# stm_board_f407.net
KiCad netlist of a schematic drawn in EAGLE
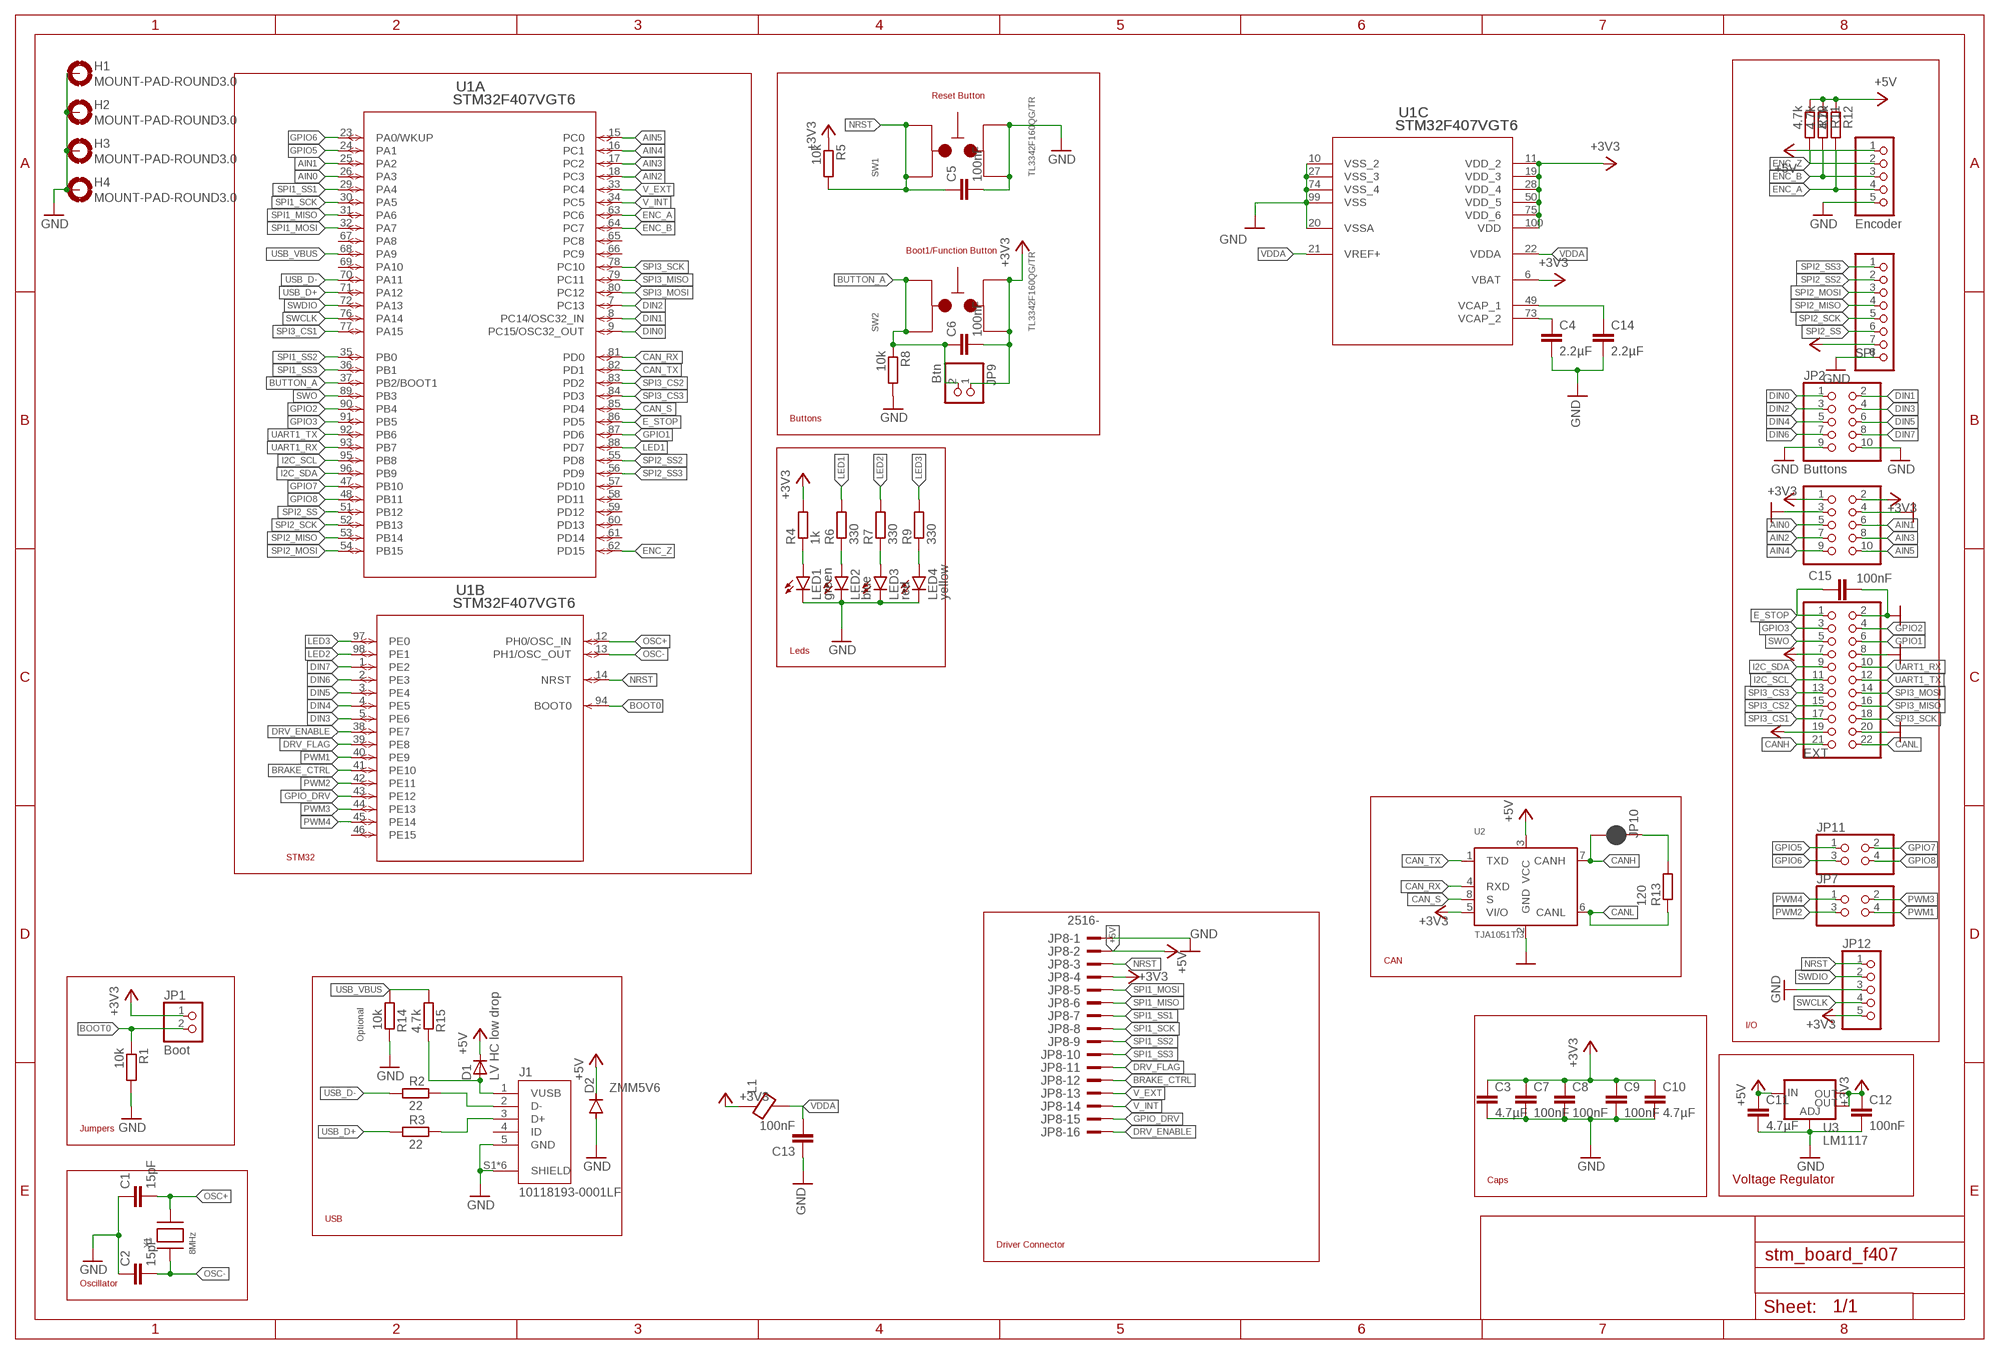
[diagram p0: schematic, sheet 1]

(export (version "E")
  (design (tool "Eeschema 10.0.6"))
  (components
    (comp (ref "C1")
      (value "15pF")
      (footprint "eagle-import:C0603")
      (libsource (lib "eagle-import") (part "C-EUC0603"))
    )
    (comp (ref "C2")
      (value "15pF")
      (footprint "eagle-import:C0603")
      (libsource (lib "eagle-import") (part "C-EUC0603"))
    )
    (comp (ref "C3")
      (value "4.7µF")
      (footprint "eagle-import:C0805")
      (libsource (lib "eagle-import") (part "C-EUC0805"))
    )
    (comp (ref "C4")
      (value "2.2µF")
      (footprint "eagle-import:C0603")
      (libsource (lib "eagle-import") (part "C-EUC0603"))
    )
    (comp (ref "C5")
      (value "100nF")
      (footprint "eagle-import:C0603")
      (libsource (lib "eagle-import") (part "C-EUC0603"))
    )
    (comp (ref "C6")
      (value "100nF")
      (footprint "eagle-import:C0603")
      (libsource (lib "eagle-import") (part "C-EUC0603"))
    )
    (comp (ref "C7")
      (value "100nF")
      (footprint "eagle-import:C0603")
      (libsource (lib "eagle-import") (part "C-EUC0603"))
    )
    (comp (ref "C8")
      (value "100nF")
      (footprint "eagle-import:C0603")
      (libsource (lib "eagle-import") (part "C-EUC0603"))
    )
    (comp (ref "C9")
      (value "100nF")
      (footprint "eagle-import:C0603")
      (libsource (lib "eagle-import") (part "C-EUC0603"))
    )
    (comp (ref "C10")
      (value "4.7µF")
      (footprint "eagle-import:C0805")
      (libsource (lib "eagle-import") (part "C-EUC0805"))
    )
    (comp (ref "C11")
      (value "4.7µF")
      (footprint "eagle-import:C0805")
      (libsource (lib "eagle-import") (part "C-EUC0805"))
    )
    (comp (ref "C12")
      (value "100nF")
      (footprint "eagle-import:C0603")
      (libsource (lib "eagle-import") (part "C-EUC0603"))
    )
    (comp (ref "C13")
      (value "100nF")
      (footprint "eagle-import:C0603")
      (libsource (lib "eagle-import") (part "C-EUC0603"))
    )
    (comp (ref "C14")
      (value "2.2µF")
      (footprint "eagle-import:C0603")
      (libsource (lib "eagle-import") (part "C-EUC0603"))
    )
    (comp (ref "C15")
      (value "100nF")
      (footprint "eagle-import:C0603")
      (libsource (lib "eagle-import") (part "C-EUC0603"))
    )
    (comp (ref "D1")
      (value "LV HC low drop")
      (footprint "eagle-import:SMADIODE")
      (libsource (lib "eagle-import") (part "DIODESMA"))
    )
    (comp (ref "D2")
      (value "ZMM5V6")
      (footprint "eagle-import:MINIMELF")
      (libsource (lib "eagle-import") (part "DIODE-MINIMELF"))
    )
    (comp (ref "H1")
      (value "MOUNT-PAD-ROUND3.0")
      (footprint "eagle-import:3,0-PAD")
      (libsource (lib "eagle-import") (part "MOUNT-PAD-ROUND3.0"))
    )
    (comp (ref "H2")
      (value "MOUNT-PAD-ROUND3.0")
      (footprint "eagle-import:3,0-PAD")
      (libsource (lib "eagle-import") (part "MOUNT-PAD-ROUND3.0"))
    )
    (comp (ref "H3")
      (value "MOUNT-PAD-ROUND3.0")
      (footprint "eagle-import:3,0-PAD")
      (libsource (lib "eagle-import") (part "MOUNT-PAD-ROUND3.0"))
    )
    (comp (ref "H4")
      (value "MOUNT-PAD-ROUND3.0")
      (footprint "eagle-import:3,0-PAD")
      (libsource (lib "eagle-import") (part "MOUNT-PAD-ROUND3.0"))
    )
    (comp (ref "J1")
      (value "10118193-0001LF")
      (footprint "eagle-import:FCI_10118193-0001LF")
      (fields (field (name "MF") "Amphenol ICC"))
      (libsource (lib "eagle-import") (part "10118193-0001LF"))
    )
    (comp (ref "JP1")
      (value "Boot")
      (footprint "eagle-import:1X02")
      (libsource (lib "eagle-import") (part "PINHD-1X2"))
    )
    (comp (ref "JP2")
      (value "Buttons")
      (footprint "eagle-import:2X05")
      (libsource (lib "eagle-import") (part "PINHD-2X5"))
    )
    (comp (ref "JP3")
      (value "Analog")
      (footprint "eagle-import:2X05")
      (libsource (lib "eagle-import") (part "PINHD-2X5"))
    )
    (comp (ref "JP4")
      (value "EXT")
      (footprint "eagle-import:2X11")
      (libsource (lib "eagle-import") (part "PINHD-2X11"))
    )
    (comp (ref "JP5")
      (value "Encoder")
      (footprint "eagle-import:1X05")
      (libsource (lib "eagle-import") (part "PINHD-1X5"))
    )
    (comp (ref "JP6")
      (value "SPI")
      (footprint "eagle-import:1X08")
      (libsource (lib "eagle-import") (part "PINHD-1X8"))
    )
    (comp (ref "JP7")
      (value "PINHD-2X2")
      (footprint "eagle-import:2X02")
      (libsource (lib "eagle-import") (part "PINHD-2X2"))
    )
    (comp (ref "JP8")
      (value "2516-")
      (footprint "eagle-import:PAK100_2500-16")
      (libsource (lib "eagle-import") (part "2516-"))
    )
    (comp (ref "JP9")
      (value "Btn")
      (footprint "eagle-import:1X02")
      (libsource (lib "eagle-import") (part "PINHD-1X2"))
    )
    (comp (ref "JP10")
      (value "JUMPER-SMT_2_NC_PASTE_NO-SILK")
      (footprint "eagle-import:SMT-JUMPER_2_NC_PASTE_NO-SILK")
      (libsource (lib "eagle-import") (part "JUMPER-SMT_2_NC_PASTE_NO-SILK"))
    )
    (comp (ref "JP11")
      (value "PINHD-2X2")
      (footprint "eagle-import:2X02")
      (libsource (lib "eagle-import") (part "PINHD-2X2"))
    )
    (comp (ref "JP12")
      (value "PINHD-1X5")
      (footprint "eagle-import:1X05")
      (libsource (lib "eagle-import") (part "PINHD-1X5"))
    )
    (comp (ref "L1")
      (value "GZ2012D601TF")
      (footprint "eagle-import:BLM21PG331SN1D")
      (fields
        (field (name "DIGIKEY_PART_NUMBER") "490-5988-2-ND")
        (field (name "MANUFACTURER") "Murata Electronics North America")
        (field (name "MPN") "BLM21PG331SN1D")
        (field (name "CREATED_BY") "PCBLayout.com")
      )
      (libsource (lib "eagle-import") (part "BLM21PG331SN1D"))
    )
    (comp (ref "LED1")
      (value "green")
      (footprint "eagle-import:SML0805")
      (libsource (lib "eagle-import") (part "LEDSML0805"))
    )
    (comp (ref "LED2")
      (value "blue")
      (footprint "eagle-import:SML0805")
      (libsource (lib "eagle-import") (part "LEDSML0805"))
    )
    (comp (ref "LED3")
      (value "red")
      (footprint "eagle-import:SML0805")
      (libsource (lib "eagle-import") (part "LEDSML0805"))
    )
    (comp (ref "LED4")
      (value "yellow")
      (footprint "eagle-import:SML0805")
      (libsource (lib "eagle-import") (part "LEDSML0805"))
    )
    (comp (ref "R1")
      (value "10k")
      (footprint "eagle-import:R0603")
      (libsource (lib "eagle-import") (part "R-EU_R0603"))
    )
    (comp (ref "R2")
      (value "22")
      (footprint "eagle-import:R0603")
      (libsource (lib "eagle-import") (part "R-EU_R0603"))
    )
    (comp (ref "R3")
      (value "22")
      (footprint "eagle-import:R0603")
      (libsource (lib "eagle-import") (part "R-EU_R0603"))
    )
    (comp (ref "R4")
      (value "1k")
      (footprint "eagle-import:R0603")
      (libsource (lib "eagle-import") (part "R-EU_R0603"))
    )
    (comp (ref "R5")
      (value "10k")
      (footprint "eagle-import:R0603")
      (libsource (lib "eagle-import") (part "R-EU_R0603"))
    )
    (comp (ref "R6")
      (value "330")
      (footprint "eagle-import:R0603")
      (libsource (lib "eagle-import") (part "R-EU_R0603"))
    )
    (comp (ref "R7")
      (value "330")
      (footprint "eagle-import:R0603")
      (libsource (lib "eagle-import") (part "R-EU_R0603"))
    )
    (comp (ref "R8")
      (value "10k")
      (footprint "eagle-import:R0603")
      (libsource (lib "eagle-import") (part "R-EU_R0603"))
    )
    (comp (ref "R9")
      (value "330")
      (footprint "eagle-import:R0603")
      (libsource (lib "eagle-import") (part "R-EU_R0603"))
    )
    (comp (ref "R10")
      (value "4.7k")
      (footprint "eagle-import:R0603")
      (libsource (lib "eagle-import") (part "R-EU_R0603"))
    )
    (comp (ref "R11")
      (value "4.7k")
      (footprint "eagle-import:R0603")
      (libsource (lib "eagle-import") (part "R-EU_R0603"))
    )
    (comp (ref "R12")
      (value "4.7k")
      (footprint "eagle-import:R0603")
      (libsource (lib "eagle-import") (part "R-EU_R0603"))
    )
    (comp (ref "R13")
      (value "120")
      (footprint "eagle-import:R0603")
      (libsource (lib "eagle-import") (part "R-EU_R0603"))
    )
    (comp (ref "R14")
      (value "10k")
      (footprint "eagle-import:R0603")
      (libsource (lib "eagle-import") (part "R-EU_R0603"))
    )
    (comp (ref "R15")
      (value "4.7k")
      (footprint "eagle-import:R0603")
      (libsource (lib "eagle-import") (part "R-EU_R0603"))
    )
    (comp (ref "SW1")
      (value "TL3342F160QG/TR")
      (footprint "eagle-import:TL3342F160QG_TR")
      (fields
        (field (name "DIGI_KEY_PART_NUMBER") "EG2531CT-ND")
        (field (name "MANUFACTURER") "E-Switch")
        (field (name "CREATED_BY") "PCBLayout.com")
      )
      (libsource (lib "eagle-import") (part "TL3342F160QG/TR"))
    )
    (comp (ref "SW2")
      (value "TL3342F160QG/TR")
      (footprint "eagle-import:TL3342F160QG_TR")
      (fields
        (field (name "DIGI_KEY_PART_NUMBER") "EG2531CT-ND")
        (field (name "MANUFACTURER") "E-Switch")
        (field (name "CREATED_BY") "PCBLayout.com")
      )
      (libsource (lib "eagle-import") (part "TL3342F160QG/TR"))
    )
    (comp (ref "U1")
      (value "STM32F407VGT6")
      (footprint "eagle-import:LQFP100-14X14MM")
      (fields (field (name "COPYRIGHT") "Copyright (C) 2018 Accelerated Designs. All rights reserved"))
      (libsource (lib "eagle-import") (part "STM32F407VGT6"))
    )
    (comp (ref "U2")
      (value "TJA1051T/3")
      (footprint "eagle-import:SOT96-1")
      (fields (field (name "MF") "NXP Semiconductors"))
      (libsource (lib "eagle-import") (part "TJA1051T/3"))
    )
    (comp (ref "U3")
      (value "LM1117")
      (footprint "eagle-import:SOT223")
      (libsource (lib "eagle-import") (part "V_REG_LM1117SOT223"))
    )
    (comp (ref "X1")
      (value "8MHz")
      (footprint "eagle-import:NX5032")
      (libsource (lib "eagle-import") (part "XTALNX5032"))
    )
  )
  (nets
    (net (code "1") (name "+3V3") (class "Default")
      (node (ref "C10") (pin "1") (pinfunction "1_1") (pintype "passive"))
      (node (ref "C12") (pin "1") (pinfunction "1_1") (pintype "passive"))
      (node (ref "C3") (pin "1") (pinfunction "1_1") (pintype "passive"))
      (node (ref "C6") (pin "2") (pinfunction "2_2") (pintype "passive"))
      (node (ref "C7") (pin "1") (pinfunction "1_1") (pintype "passive"))
      (node (ref "C8") (pin "1") (pinfunction "1_1") (pintype "passive"))
      (node (ref "C9") (pin "1") (pinfunction "1_1") (pintype "passive"))
      (node (ref "JP1") (pin "1") (pinfunction "1_1") (pintype "passive"))
      (node (ref "JP12") (pin "5") (pinfunction "5_5") (pintype "passive"))
      (node (ref "JP3") (pin "1") (pinfunction "1_1") (pintype "passive"))
      (node (ref "JP3") (pin "2") (pinfunction "2_2") (pintype "passive"))
      (node (ref "JP4") (pin "7") (pinfunction "7_7") (pintype "passive"))
      (node (ref "JP6") (pin "7") (pinfunction "7_7") (pintype "passive"))
      (node (ref "JP8") (pin "4") (pinfunction "KL_4") (pintype "passive"))
      (node (ref "JP9") (pin "1") (pinfunction "1_1") (pintype "passive"))
      (node (ref "L1") (pin "1") (pinfunction "1_1") (pintype "passive"))
      (node (ref "R4") (pin "2") (pinfunction "2_2") (pintype "passive"))
      (node (ref "R5") (pin "1") (pinfunction "1_1") (pintype "passive"))
      (node (ref "SW2") (pin "1") (pinfunction "1_1") (pintype "passive"))
      (node (ref "SW2") (pin "2") (pinfunction "2_2") (pintype "passive"))
      (node (ref "U1") (pin "100") (pinfunction "VDD_100") (pintype "power_in"))
      (node (ref "U1") (pin "11") (pinfunction "VDD_2_11") (pintype "power_in"))
      (node (ref "U1") (pin "19") (pinfunction "VDD_3_19") (pintype "power_in"))
      (node (ref "U1") (pin "28") (pinfunction "VDD_4_28") (pintype "power_in"))
      (node (ref "U1") (pin "50") (pinfunction "VDD_5_50") (pintype "power_in"))
      (node (ref "U1") (pin "6") (pinfunction "VBAT_6") (pintype "power_in"))
      (node (ref "U1") (pin "75") (pinfunction "VDD_6_75") (pintype "power_in"))
      (node (ref "U2") (pin "5") (pinfunction "VI/O_5") (pintype "passive"))
      (node (ref "U3") (pin "2") (pinfunction "OUT_2") (pintype "output"))
      (node (ref "U3") (pin "4") (pinfunction "OUT_4") (pintype "output"))
    )
    (net (code "2") (name "+5V") (class "Default")
      (node (ref "C11") (pin "1") (pinfunction "1_1") (pintype "passive"))
      (node (ref "D1") (pin "C") (pinfunction "C_C") (pintype "passive"))
      (node (ref "D2") (pin "C") (pinfunction "C_C") (pintype "passive"))
      (node (ref "JP4") (pin "19") (pinfunction "19_19") (pintype "passive"))
      (node (ref "JP5") (pin "1") (pinfunction "1_1") (pintype "passive"))
      (node (ref "JP8") (pin "2") (pinfunction "KL_2") (pintype "passive"))
      (node (ref "R10") (pin "1") (pinfunction "1_1") (pintype "passive"))
      (node (ref "R11") (pin "1") (pinfunction "1_1") (pintype "passive"))
      (node (ref "R12") (pin "1") (pinfunction "1_1") (pintype "passive"))
      (node (ref "U2") (pin "3") (pinfunction "VCC_3") (pintype "bidirectional"))
      (node (ref "U3") (pin "3") (pinfunction "IN_3") (pintype "input"))
    )
    (net (code "3") (name "AIN0") (class "Default")
      (node (ref "JP3") (pin "5") (pinfunction "5_5") (pintype "passive"))
      (node (ref "U1") (pin "26") (pinfunction "PA3_26") (pintype "bidirectional"))
    )
    (net (code "4") (name "AIN1") (class "Default")
      (node (ref "JP3") (pin "6") (pinfunction "6_6") (pintype "passive"))
      (node (ref "U1") (pin "25") (pinfunction "PA2_25") (pintype "bidirectional"))
    )
    (net (code "5") (name "AIN2") (class "Default")
      (node (ref "JP3") (pin "7") (pinfunction "7_7") (pintype "passive"))
      (node (ref "U1") (pin "18") (pinfunction "PC3_18") (pintype "bidirectional"))
    )
    (net (code "6") (name "AIN3") (class "Default")
      (node (ref "JP3") (pin "8") (pinfunction "8_8") (pintype "passive"))
      (node (ref "U1") (pin "17") (pinfunction "PC2_17") (pintype "bidirectional"))
    )
    (net (code "7") (name "AIN4") (class "Default")
      (node (ref "JP3") (pin "9") (pinfunction "9_9") (pintype "passive"))
      (node (ref "U1") (pin "16") (pinfunction "PC1_16") (pintype "bidirectional"))
    )
    (net (code "8") (name "AIN5") (class "Default")
      (node (ref "JP3") (pin "10") (pinfunction "10_10") (pintype "passive"))
      (node (ref "U1") (pin "15") (pinfunction "PC0_15") (pintype "bidirectional"))
    )
    (net (code "9") (name "BOOT0") (class "Default")
      (node (ref "JP1") (pin "2") (pinfunction "2_2") (pintype "passive"))
      (node (ref "R1") (pin "1") (pinfunction "1_1") (pintype "passive"))
      (node (ref "U1") (pin "94") (pinfunction "BOOT0_94") (pintype "input"))
    )
    (net (code "10") (name "BRAKE_CTRL") (class "Default")
      (node (ref "JP8") (pin "12") (pinfunction "KL_12") (pintype "passive"))
      (node (ref "U1") (pin "41") (pinfunction "PE10_41") (pintype "bidirectional"))
    )
    (net (code "11") (name "BUTTON_A") (class "Default")
      (node (ref "C6") (pin "1") (pinfunction "1_1") (pintype "passive"))
      (node (ref "JP9") (pin "2") (pinfunction "2_2") (pintype "passive"))
      (node (ref "R8") (pin "1") (pinfunction "1_1") (pintype "passive"))
      (node (ref "SW2") (pin "3") (pinfunction "3_3") (pintype "passive"))
      (node (ref "SW2") (pin "4") (pinfunction "4_4") (pintype "passive"))
      (node (ref "U1") (pin "37") (pinfunction "PB2/BOOT1_37") (pintype "bidirectional"))
    )
    (net (code "12") (name "CANH") (class "Default")
      (node (ref "JP10") (pin "2") (pinfunction "2_2") (pintype "passive"))
      (node (ref "JP4") (pin "21") (pinfunction "21_21") (pintype "passive"))
      (node (ref "U2") (pin "7") (pinfunction "CANH_7") (pintype "bidirectional"))
    )
    (net (code "13") (name "CANL") (class "Default")
      (node (ref "JP4") (pin "22") (pinfunction "22_22") (pintype "passive"))
      (node (ref "R13") (pin "1") (pinfunction "1_1") (pintype "passive"))
      (node (ref "U2") (pin "6") (pinfunction "CANL_6") (pintype "bidirectional"))
    )
    (net (code "14") (name "CAN_RX") (class "Default")
      (node (ref "U1") (pin "81") (pinfunction "PD0_81") (pintype "bidirectional"))
      (node (ref "U2") (pin "4") (pinfunction "RXD_4") (pintype "bidirectional"))
    )
    (net (code "15") (name "CAN_S") (class "Default")
      (node (ref "U1") (pin "85") (pinfunction "PD4_85") (pintype "bidirectional"))
      (node (ref "U2") (pin "8") (pinfunction "S_8") (pintype "power_in"))
    )
    (net (code "16") (name "CAN_TX") (class "Default")
      (node (ref "U1") (pin "82") (pinfunction "PD1_82") (pintype "bidirectional"))
      (node (ref "U2") (pin "1") (pinfunction "TXD_1") (pintype "output"))
    )
    (net (code "17") (name "DIN0") (class "Default")
      (node (ref "JP2") (pin "1") (pinfunction "1_1") (pintype "passive"))
      (node (ref "U1") (pin "9") (pinfunction "PC15/OSC32_OUT_9") (pintype "bidirectional"))
    )
    (net (code "18") (name "DIN1") (class "Default")
      (node (ref "JP2") (pin "2") (pinfunction "2_2") (pintype "passive"))
      (node (ref "U1") (pin "8") (pinfunction "PC14/OSC32_IN_8") (pintype "bidirectional"))
    )
    (net (code "19") (name "DIN2") (class "Default")
      (node (ref "JP2") (pin "3") (pinfunction "3_3") (pintype "passive"))
      (node (ref "U1") (pin "7") (pinfunction "PC13_7") (pintype "bidirectional"))
    )
    (net (code "20") (name "DIN3") (class "Default")
      (node (ref "JP2") (pin "4") (pinfunction "4_4") (pintype "passive"))
      (node (ref "U1") (pin "5") (pinfunction "PE6_5") (pintype "bidirectional"))
    )
    (net (code "21") (name "DIN4") (class "Default")
      (node (ref "JP2") (pin "5") (pinfunction "5_5") (pintype "passive"))
      (node (ref "U1") (pin "4") (pinfunction "PE5_4") (pintype "bidirectional"))
    )
    (net (code "22") (name "DIN5") (class "Default")
      (node (ref "JP2") (pin "6") (pinfunction "6_6") (pintype "passive"))
      (node (ref "U1") (pin "3") (pinfunction "PE4_3") (pintype "bidirectional"))
    )
    (net (code "23") (name "DIN6") (class "Default")
      (node (ref "JP2") (pin "7") (pinfunction "7_7") (pintype "passive"))
      (node (ref "U1") (pin "2") (pinfunction "PE3_2") (pintype "bidirectional"))
    )
    (net (code "24") (name "DIN7") (class "Default")
      (node (ref "JP2") (pin "8") (pinfunction "8_8") (pintype "passive"))
      (node (ref "U1") (pin "1") (pinfunction "PE2_1") (pintype "bidirectional"))
    )
    (net (code "25") (name "DRV_ENABLE") (class "Default")
      (node (ref "JP8") (pin "16") (pinfunction "KL_16") (pintype "passive"))
      (node (ref "U1") (pin "38") (pinfunction "PE7_38") (pintype "bidirectional"))
    )
    (net (code "26") (name "DRV_FLAG") (class "Default")
      (node (ref "JP8") (pin "11") (pinfunction "KL_11") (pintype "passive"))
      (node (ref "U1") (pin "39") (pinfunction "PE8_39") (pintype "bidirectional"))
    )
    (net (code "27") (name "ENC_A") (class "Default")
      (node (ref "JP5") (pin "4") (pinfunction "4_4") (pintype "passive"))
      (node (ref "R12") (pin "2") (pinfunction "2_2") (pintype "passive"))
      (node (ref "U1") (pin "63") (pinfunction "PC6_63") (pintype "bidirectional"))
    )
    (net (code "28") (name "ENC_B") (class "Default")
      (node (ref "JP5") (pin "3") (pinfunction "3_3") (pintype "passive"))
      (node (ref "R11") (pin "2") (pinfunction "2_2") (pintype "passive"))
      (node (ref "U1") (pin "64") (pinfunction "PC7_64") (pintype "bidirectional"))
    )
    (net (code "29") (name "ENC_Z") (class "Default")
      (node (ref "JP5") (pin "2") (pinfunction "2_2") (pintype "passive"))
      (node (ref "R10") (pin "2") (pinfunction "2_2") (pintype "passive"))
      (node (ref "U1") (pin "62") (pinfunction "PD15_62") (pintype "bidirectional"))
    )
    (net (code "30") (name "E_STOP") (class "Default")
      (node (ref "C15") (pin "1") (pinfunction "1_1") (pintype "passive"))
      (node (ref "JP4") (pin "1") (pinfunction "1_1") (pintype "passive"))
      (node (ref "U1") (pin "86") (pinfunction "PD5_86") (pintype "bidirectional"))
    )
    (net (code "31") (name "GND") (class "Default")
      (node (ref "C1") (pin "1") (pinfunction "1_1") (pintype "passive"))
      (node (ref "C10") (pin "2") (pinfunction "2_2") (pintype "passive"))
      (node (ref "C11") (pin "2") (pinfunction "2_2") (pintype "passive"))
      (node (ref "C12") (pin "2") (pinfunction "2_2") (pintype "passive"))
      (node (ref "C13") (pin "1") (pinfunction "1_1") (pintype "passive"))
      (node (ref "C14") (pin "2") (pinfunction "2_2") (pintype "passive"))
      (node (ref "C15") (pin "2") (pinfunction "2_2") (pintype "passive"))
      (node (ref "C2") (pin "1") (pinfunction "1_1") (pintype "passive"))
      (node (ref "C3") (pin "2") (pinfunction "2_2") (pintype "passive"))
      (node (ref "C4") (pin "2") (pinfunction "2_2") (pintype "passive"))
      (node (ref "C5") (pin "2") (pinfunction "2_2") (pintype "passive"))
      (node (ref "C7") (pin "2") (pinfunction "2_2") (pintype "passive"))
      (node (ref "C8") (pin "2") (pinfunction "2_2") (pintype "passive"))
      (node (ref "C9") (pin "2") (pinfunction "2_2") (pintype "passive"))
      (node (ref "D2") (pin "A") (pinfunction "A_A") (pintype "passive"))
      (node (ref "H1") (pin "B3,0") (pinfunction "MOUNT_B3,0") (pintype "passive"))
      (node (ref "H2") (pin "B3,0") (pinfunction "MOUNT_B3,0") (pintype "passive"))
      (node (ref "H3") (pin "B3,0") (pinfunction "MOUNT_B3,0") (pintype "passive"))
      (node (ref "H4") (pin "B3,0") (pinfunction "MOUNT_B3,0") (pintype "passive"))
      (node (ref "J1") (pin "5") (pinfunction "GND_5") (pintype "passive"))
      (node (ref "J1") (pin "S1") (pinfunction "SHIELD_S1") (pintype "passive"))
      (node (ref "J1") (pin "S2") (pinfunction "SHIELD_S2") (pintype "passive"))
      (node (ref "J1") (pin "S3") (pinfunction "SHIELD_S3") (pintype "passive"))
      (node (ref "J1") (pin "S4") (pinfunction "SHIELD_S4") (pintype "passive"))
      (node (ref "J1") (pin "S5") (pinfunction "SHIELD_S5") (pintype "passive"))
      (node (ref "J1") (pin "S6") (pinfunction "SHIELD_S6") (pintype "passive"))
      (node (ref "JP12") (pin "3") (pinfunction "3_3") (pintype "passive"))
      (node (ref "JP2") (pin "10") (pinfunction "10_10") (pintype "passive"))
      (node (ref "JP2") (pin "9") (pinfunction "9_9") (pintype "passive"))
      (node (ref "JP3") (pin "3") (pinfunction "3_3") (pintype "passive"))
      (node (ref "JP3") (pin "4") (pinfunction "4_4") (pintype "passive"))
      (node (ref "JP4") (pin "2") (pinfunction "2_2") (pintype "passive"))
      (node (ref "JP4") (pin "20") (pinfunction "20_20") (pintype "passive"))
      (node (ref "JP4") (pin "8") (pinfunction "8_8") (pintype "passive"))
      (node (ref "JP5") (pin "5") (pinfunction "5_5") (pintype "passive"))
      (node (ref "JP6") (pin "8") (pinfunction "8_8") (pintype "passive"))
      (node (ref "JP8") (pin "1") (pinfunction "KL_1") (pintype "passive"))
      (node (ref "LED1") (pin "C") (pinfunction "C_C") (pintype "passive"))
      (node (ref "LED2") (pin "C") (pinfunction "C_C") (pintype "passive"))
      (node (ref "LED3") (pin "C") (pinfunction "C_C") (pintype "passive"))
      (node (ref "LED4") (pin "C") (pinfunction "C_C") (pintype "passive"))
      (node (ref "R1") (pin "2") (pinfunction "2_2") (pintype "passive"))
      (node (ref "R14") (pin "2") (pinfunction "2_2") (pintype "passive"))
      (node (ref "R8") (pin "2") (pinfunction "2_2") (pintype "passive"))
      (node (ref "SW1") (pin "1") (pinfunction "1_1") (pintype "passive"))
      (node (ref "SW1") (pin "2") (pinfunction "2_2") (pintype "passive"))
      (node (ref "U1") (pin "10") (pinfunction "VSS_2_10") (pintype "power_in"))
      (node (ref "U1") (pin "20") (pinfunction "VSSA_20") (pintype "power_in"))
      (node (ref "U1") (pin "27") (pinfunction "VSS_3_27") (pintype "power_in"))
      (node (ref "U1") (pin "74") (pinfunction "VSS_4_74") (pintype "power_in"))
      (node (ref "U1") (pin "99") (pinfunction "VSS_99") (pintype "power_in"))
      (node (ref "U2") (pin "2") (pinfunction "GND_2") (pintype "bidirectional"))
      (node (ref "U3") (pin "1") (pinfunction "ADJ_1") (pintype "input"))
    )
    (net (code "32") (name "GPIO1") (class "Default")
      (node (ref "JP4") (pin "6") (pinfunction "6_6") (pintype "passive"))
      (node (ref "U1") (pin "87") (pinfunction "PD6_87") (pintype "bidirectional"))
    )
    (net (code "33") (name "GPIO2") (class "Default")
      (node (ref "JP4") (pin "4") (pinfunction "4_4") (pintype "passive"))
      (node (ref "U1") (pin "90") (pinfunction "PB4_90") (pintype "bidirectional"))
    )
    (net (code "34") (name "GPIO3") (class "Default")
      (node (ref "JP4") (pin "3") (pinfunction "3_3") (pintype "passive"))
      (node (ref "U1") (pin "91") (pinfunction "PB5_91") (pintype "bidirectional"))
    )
    (net (code "35") (name "GPIO5") (class "Default")
      (node (ref "JP11") (pin "1") (pinfunction "1_1") (pintype "passive"))
      (node (ref "U1") (pin "24") (pinfunction "PA1_24") (pintype "bidirectional"))
    )
    (net (code "36") (name "GPIO6") (class "Default")
      (node (ref "JP11") (pin "3") (pinfunction "3_3") (pintype "passive"))
      (node (ref "U1") (pin "23") (pinfunction "PA0/WKUP_23") (pintype "bidirectional"))
    )
    (net (code "37") (name "GPIO7") (class "Default")
      (node (ref "JP11") (pin "2") (pinfunction "2_2") (pintype "passive"))
      (node (ref "U1") (pin "47") (pinfunction "PB10_47") (pintype "bidirectional"))
    )
    (net (code "38") (name "GPIO8") (class "Default")
      (node (ref "JP11") (pin "4") (pinfunction "4_4") (pintype "passive"))
      (node (ref "U1") (pin "48") (pinfunction "PB11_48") (pintype "bidirectional"))
    )
    (net (code "39") (name "GPIO_DRV") (class "Default")
      (node (ref "JP8") (pin "15") (pinfunction "KL_15") (pintype "passive"))
      (node (ref "U1") (pin "43") (pinfunction "PE12_43") (pintype "bidirectional"))
    )
    (net (code "40") (name "I2C_SCL") (class "Default")
      (node (ref "JP4") (pin "11") (pinfunction "11_11") (pintype "passive"))
      (node (ref "U1") (pin "95") (pinfunction "PB8_95") (pintype "bidirectional"))
    )
    (net (code "41") (name "I2C_SDA") (class "Default")
      (node (ref "JP4") (pin "9") (pinfunction "9_9") (pintype "passive"))
      (node (ref "U1") (pin "96") (pinfunction "PB9_96") (pintype "bidirectional"))
    )
    (net (code "42") (name "LED1") (class "Default")
      (node (ref "R6") (pin "2") (pinfunction "2_2") (pintype "passive"))
      (node (ref "U1") (pin "88") (pinfunction "PD7_88") (pintype "bidirectional"))
    )
    (net (code "43") (name "LED2") (class "Default")
      (node (ref "R7") (pin "2") (pinfunction "2_2") (pintype "passive"))
      (node (ref "U1") (pin "98") (pinfunction "PE1_98") (pintype "bidirectional"))
    )
    (net (code "44") (name "LED3") (class "Default")
      (node (ref "R9") (pin "2") (pinfunction "2_2") (pintype "passive"))
      (node (ref "U1") (pin "97") (pinfunction "PE0_97") (pintype "bidirectional"))
    )
    (net (code "45") (name "NRST") (class "Default")
      (node (ref "C5") (pin "1") (pinfunction "1_1") (pintype "passive"))
      (node (ref "JP12") (pin "1") (pinfunction "1_1") (pintype "passive"))
      (node (ref "JP8") (pin "3") (pinfunction "KL_3") (pintype "passive"))
      (node (ref "R5") (pin "2") (pinfunction "2_2") (pintype "passive"))
      (node (ref "SW1") (pin "3") (pinfunction "3_3") (pintype "passive"))
      (node (ref "SW1") (pin "4") (pinfunction "4_4") (pintype "passive"))
      (node (ref "U1") (pin "14") (pinfunction "NRST_14") (pintype "bidirectional"))
    )
    (net (code "46") (name "Net-(J1-D+)") (class "Default")
      (node (ref "J1") (pin "3") (pinfunction "D+_3") (pintype "passive"))
      (node (ref "R3") (pin "2") (pinfunction "2_2") (pintype "passive"))
    )
    (net (code "47") (name "Net-(J1-D-)") (class "Default")
      (node (ref "J1") (pin "2") (pinfunction "D-_2") (pintype "passive"))
      (node (ref "R2") (pin "2") (pinfunction "2_2") (pintype "passive"))
    )
    (net (code "48") (name "Net-(J1-VUSB)") (class "Default")
      (node (ref "D1") (pin "A") (pinfunction "A_A") (pintype "passive"))
      (node (ref "J1") (pin "1") (pinfunction "VUSB_1") (pintype "passive"))
      (node (ref "R15") (pin "2") (pinfunction "2_2") (pintype "passive"))
    )
    (net (code "49") (name "Net-(JP10-Pad1)") (class "Default")
      (node (ref "JP10") (pin "1") (pinfunction "1_1") (pintype "passive"))
      (node (ref "R13") (pin "2") (pinfunction "2_2") (pintype "passive"))
    )
    (net (code "50") (name "Net-(LED1-PadA)") (class "Default")
      (node (ref "LED1") (pin "A") (pinfunction "A_A") (pintype "passive"))
      (node (ref "R4") (pin "1") (pinfunction "1_1") (pintype "passive"))
    )
    (net (code "51") (name "Net-(LED2-PadA)") (class "Default")
      (node (ref "LED2") (pin "A") (pinfunction "A_A") (pintype "passive"))
      (node (ref "R6") (pin "1") (pinfunction "1_1") (pintype "passive"))
    )
    (net (code "52") (name "Net-(LED3-PadA)") (class "Default")
      (node (ref "LED3") (pin "A") (pinfunction "A_A") (pintype "passive"))
      (node (ref "R7") (pin "1") (pinfunction "1_1") (pintype "passive"))
    )
    (net (code "53") (name "Net-(LED4-PadA)") (class "Default")
      (node (ref "LED4") (pin "A") (pinfunction "A_A") (pintype "passive"))
      (node (ref "R9") (pin "1") (pinfunction "1_1") (pintype "passive"))
    )
    (net (code "54") (name "Net-(U1C-VCAP_1)") (class "Default")
      (node (ref "C14") (pin "1") (pinfunction "1_1") (pintype "passive"))
      (node (ref "U1") (pin "49") (pinfunction "VCAP_1_49") (pintype "power_in"))
    )
    (net (code "55") (name "Net-(U1C-VCAP_2)") (class "Default")
      (node (ref "C4") (pin "1") (pinfunction "1_1") (pintype "passive"))
      (node (ref "U1") (pin "73") (pinfunction "VCAP_2_73") (pintype "power_in"))
    )
    (net (code "56") (name "OSC+") (class "Default")
      (node (ref "C1") (pin "2") (pinfunction "2_2") (pintype "passive"))
      (node (ref "U1") (pin "12") (pinfunction "PH0/OSC_IN_12") (pintype "bidirectional"))
      (node (ref "X1") (pin "P$2") (pinfunction "P$2_P$2") (pintype "bidirectional"))
    )
    (net (code "57") (name "OSC-") (class "Default")
      (node (ref "C2") (pin "2") (pinfunction "2_2") (pintype "passive"))
      (node (ref "U1") (pin "13") (pinfunction "PH1/OSC_OUT_13") (pintype "bidirectional"))
      (node (ref "X1") (pin "P$1") (pinfunction "P$1_P$1") (pintype "bidirectional"))
    )
    (net (code "58") (name "PWM1") (class "Default")
      (node (ref "JP7") (pin "4") (pinfunction "4_4") (pintype "passive"))
      (node (ref "U1") (pin "40") (pinfunction "PE9_40") (pintype "bidirectional"))
    )
    (net (code "59") (name "PWM2") (class "Default")
      (node (ref "JP7") (pin "3") (pinfunction "3_3") (pintype "passive"))
      (node (ref "U1") (pin "42") (pinfunction "PE11_42") (pintype "bidirectional"))
    )
    (net (code "60") (name "PWM3") (class "Default")
      (node (ref "JP7") (pin "2") (pinfunction "2_2") (pintype "passive"))
      (node (ref "U1") (pin "44") (pinfunction "PE13_44") (pintype "bidirectional"))
    )
    (net (code "61") (name "PWM4") (class "Default")
      (node (ref "JP7") (pin "1") (pinfunction "1_1") (pintype "passive"))
      (node (ref "U1") (pin "45") (pinfunction "PE14_45") (pintype "bidirectional"))
    )
    (net (code "62") (name "SPI1_MISO") (class "Default")
      (node (ref "JP8") (pin "6") (pinfunction "KL_6") (pintype "passive"))
      (node (ref "U1") (pin "31") (pinfunction "PA6_31") (pintype "bidirectional"))
    )
    (net (code "63") (name "SPI1_MOSI") (class "Default")
      (node (ref "JP8") (pin "5") (pinfunction "KL_5") (pintype "passive"))
      (node (ref "U1") (pin "32") (pinfunction "PA7_32") (pintype "bidirectional"))
    )
    (net (code "64") (name "SPI1_SCK") (class "Default")
      (node (ref "JP8") (pin "8") (pinfunction "KL_8") (pintype "passive"))
      (node (ref "U1") (pin "30") (pinfunction "PA5_30") (pintype "bidirectional"))
    )
    (net (code "65") (name "SPI1_SS1") (class "Default")
      (node (ref "JP8") (pin "7") (pinfunction "KL_7") (pintype "passive"))
      (node (ref "U1") (pin "29") (pinfunction "PA4_29") (pintype "bidirectional"))
    )
    (net (code "66") (name "SPI1_SS2") (class "Default")
      (node (ref "JP8") (pin "9") (pinfunction "KL_9") (pintype "passive"))
      (node (ref "U1") (pin "35") (pinfunction "PB0_35") (pintype "bidirectional"))
    )
    (net (code "67") (name "SPI1_SS3") (class "Default")
      (node (ref "JP8") (pin "10") (pinfunction "KL_10") (pintype "passive"))
      (node (ref "U1") (pin "36") (pinfunction "PB1_36") (pintype "bidirectional"))
    )
    (net (code "68") (name "SPI2_MISO") (class "Default")
      (node (ref "JP6") (pin "4") (pinfunction "4_4") (pintype "passive"))
      (node (ref "U1") (pin "53") (pinfunction "PB14_53") (pintype "bidirectional"))
    )
    (net (code "69") (name "SPI2_MOSI") (class "Default")
      (node (ref "JP6") (pin "3") (pinfunction "3_3") (pintype "passive"))
      (node (ref "U1") (pin "54") (pinfunction "PB15_54") (pintype "bidirectional"))
    )
    (net (code "70") (name "SPI2_SCK") (class "Default")
      (node (ref "JP6") (pin "5") (pinfunction "5_5") (pintype "passive"))
      (node (ref "U1") (pin "52") (pinfunction "PB13_52") (pintype "bidirectional"))
    )
    (net (code "71") (name "SPI2_SS") (class "Default")
      (node (ref "JP6") (pin "6") (pinfunction "6_6") (pintype "passive"))
      (node (ref "U1") (pin "51") (pinfunction "PB12_51") (pintype "bidirectional"))
    )
    (net (code "72") (name "SPI2_SS2") (class "Default")
      (node (ref "JP6") (pin "2") (pinfunction "2_2") (pintype "passive"))
      (node (ref "U1") (pin "55") (pinfunction "PD8_55") (pintype "bidirectional"))
    )
    (net (code "73") (name "SPI2_SS3") (class "Default")
      (node (ref "JP6") (pin "1") (pinfunction "1_1") (pintype "passive"))
      (node (ref "U1") (pin "56") (pinfunction "PD9_56") (pintype "bidirectional"))
    )
    (net (code "74") (name "SPI3_CS1") (class "Default")
      (node (ref "JP4") (pin "17") (pinfunction "17_17") (pintype "passive"))
      (node (ref "U1") (pin "77") (pinfunction "PA15_77") (pintype "bidirectional"))
    )
    (net (code "75") (name "SPI3_CS2") (class "Default")
      (node (ref "JP4") (pin "15") (pinfunction "15_15") (pintype "passive"))
      (node (ref "U1") (pin "83") (pinfunction "PD2_83") (pintype "bidirectional"))
    )
    (net (code "76") (name "SPI3_CS3") (class "Default")
      (node (ref "JP4") (pin "13") (pinfunction "13_13") (pintype "passive"))
      (node (ref "U1") (pin "84") (pinfunction "PD3_84") (pintype "bidirectional"))
    )
    (net (code "77") (name "SPI3_MISO") (class "Default")
      (node (ref "JP4") (pin "16") (pinfunction "16_16") (pintype "passive"))
      (node (ref "U1") (pin "79") (pinfunction "PC11_79") (pintype "bidirectional"))
    )
    (net (code "78") (name "SPI3_MOSI") (class "Default")
      (node (ref "JP4") (pin "14") (pinfunction "14_14") (pintype "passive"))
      (node (ref "U1") (pin "80") (pinfunction "PC12_80") (pintype "bidirectional"))
    )
    (net (code "79") (name "SPI3_SCK") (class "Default")
      (node (ref "JP4") (pin "18") (pinfunction "18_18") (pintype "passive"))
      (node (ref "U1") (pin "78") (pinfunction "PC10_78") (pintype "bidirectional"))
    )
    (net (code "80") (name "SWCLK") (class "Default")
      (node (ref "JP12") (pin "4") (pinfunction "4_4") (pintype "passive"))
      (node (ref "U1") (pin "76") (pinfunction "PA14_76") (pintype "bidirectional"))
    )
    (net (code "81") (name "SWDIO") (class "Default")
      (node (ref "JP12") (pin "2") (pinfunction "2_2") (pintype "passive"))
      (node (ref "U1") (pin "72") (pinfunction "PA13_72") (pintype "bidirectional"))
    )
    (net (code "82") (name "SWO") (class "Default")
      (node (ref "JP4") (pin "5") (pinfunction "5_5") (pintype "passive"))
      (node (ref "U1") (pin "89") (pinfunction "PB3_89") (pintype "bidirectional"))
    )
    (net (code "83") (name "UART1_RX") (class "Default")
      (node (ref "JP4") (pin "10") (pinfunction "10_10") (pintype "passive"))
      (node (ref "U1") (pin "93") (pinfunction "PB7_93") (pintype "bidirectional"))
    )
    (net (code "84") (name "UART1_TX") (class "Default")
      (node (ref "JP4") (pin "12") (pinfunction "12_12") (pintype "passive"))
      (node (ref "U1") (pin "92") (pinfunction "PB6_92") (pintype "bidirectional"))
    )
    (net (code "85") (name "USB_D+") (class "Default")
      (node (ref "R3") (pin "1") (pinfunction "1_1") (pintype "passive"))
      (node (ref "U1") (pin "71") (pinfunction "PA12_71") (pintype "bidirectional"))
    )
    (net (code "86") (name "USB_D-") (class "Default")
      (node (ref "R2") (pin "1") (pinfunction "1_1") (pintype "passive"))
      (node (ref "U1") (pin "70") (pinfunction "PA11_70") (pintype "bidirectional"))
    )
    (net (code "87") (name "USB_VBUS") (class "Default")
      (node (ref "R14") (pin "1") (pinfunction "1_1") (pintype "passive"))
      (node (ref "R15") (pin "1") (pinfunction "1_1") (pintype "passive"))
      (node (ref "U1") (pin "68") (pinfunction "PA9_68") (pintype "bidirectional"))
    )
    (net (code "88") (name "VDDA") (class "Default")
      (node (ref "C13") (pin "2") (pinfunction "2_2") (pintype "passive"))
      (node (ref "L1") (pin "2") (pinfunction "2_2") (pintype "passive"))
      (node (ref "U1") (pin "21") (pinfunction "VREF+_21") (pintype "power_in"))
      (node (ref "U1") (pin "22") (pinfunction "VDDA_22") (pintype "power_in"))
    )
    (net (code "89") (name "V_EXT") (class "Default")
      (node (ref "JP8") (pin "13") (pinfunction "KL_13") (pintype "passive"))
      (node (ref "U1") (pin "33") (pinfunction "PC4_33") (pintype "bidirectional"))
    )
    (net (code "90") (name "V_INT") (class "Default")
      (node (ref "JP8") (pin "14") (pinfunction "KL_14") (pintype "passive"))
      (node (ref "U1") (pin "34") (pinfunction "PC5_34") (pintype "bidirectional"))
    )
    (net (code "91") (name "unconnected-(J1-ID-Pad4)") (class "Default")
      (node (ref "J1") (pin "4") (pinfunction "ID_4") (pintype "passive"))
    )
    (net (code "92") (name "unconnected-(U1A-PA8-Pad67)") (class "Default")
      (node (ref "U1") (pin "67") (pinfunction "PA8_67") (pintype "bidirectional"))
    )
    (net (code "93") (name "unconnected-(U1A-PA10-Pad69)") (class "Default")
      (node (ref "U1") (pin "69") (pinfunction "PA10_69") (pintype "bidirectional"))
    )
    (net (code "94") (name "unconnected-(U1A-PC8-Pad65)") (class "Default")
      (node (ref "U1") (pin "65") (pinfunction "PC8_65") (pintype "bidirectional"))
    )
    (net (code "95") (name "unconnected-(U1A-PC9-Pad66)") (class "Default")
      (node (ref "U1") (pin "66") (pinfunction "PC9_66") (pintype "bidirectional"))
    )
    (net (code "96") (name "unconnected-(U1A-PD10-Pad57)") (class "Default")
      (node (ref "U1") (pin "57") (pinfunction "PD10_57") (pintype "bidirectional"))
    )
    (net (code "97") (name "unconnected-(U1A-PD11-Pad58)") (class "Default")
      (node (ref "U1") (pin "58") (pinfunction "PD11_58") (pintype "bidirectional"))
    )
    (net (code "98") (name "unconnected-(U1A-PD12-Pad59)") (class "Default")
      (node (ref "U1") (pin "59") (pinfunction "PD12_59") (pintype "bidirectional"))
    )
    (net (code "99") (name "unconnected-(U1A-PD13-Pad60)") (class "Default")
      (node (ref "U1") (pin "60") (pinfunction "PD13_60") (pintype "bidirectional"))
    )
    (net (code "100") (name "unconnected-(U1A-PD14-Pad61)") (class "Default")
      (node (ref "U1") (pin "61") (pinfunction "PD14_61") (pintype "bidirectional"))
    )
    (net (code "101") (name "unconnected-(U1B-PE15-Pad46)") (class "Default")
      (node (ref "U1") (pin "46") (pinfunction "PE15_46") (pintype "bidirectional"))
    )
  )
)
